# Power_Supply.net
KiCad netlist of a schematic drawn in Altium Designer
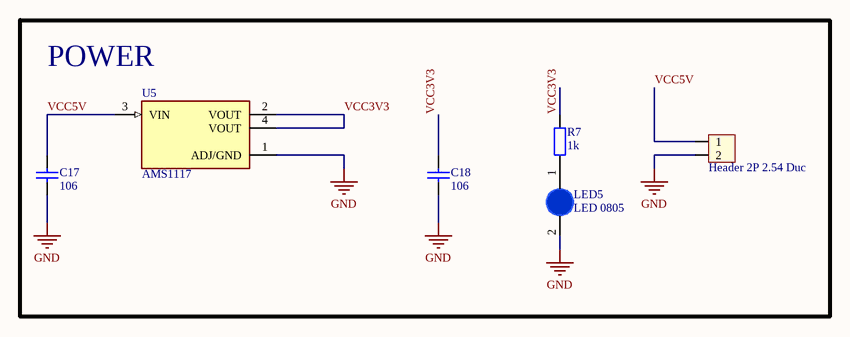
[diagram p0: Power_Supply.SchDoc]

(export (version "E")
  (design (tool "Eeschema 10.0.6"))
  (components
    (comp (ref "C17")
      (value "106")
      (footprint "tu 0603")
      (description "Dán")
      (libsource (lib "Tu dien") (part "Tu 0603 106 16V 20%"))
    )
    (comp (ref "C18")
      (value "106")
      (footprint "tu 0603")
      (description "Dán")
      (libsource (lib "Tu dien") (part "Tu 0603 106 16V 20%"))
    )
    (comp (ref "H2")
      (value "Header 2P 2.54 Duc")
      (footprint "XH2.54M-2")
      (description "Cắm")
      (libsource (lib "Header") (part "Header 2P 2.54 Duc Thang"))
    )
    (comp (ref "LED5")
      (value "LED 0805")
      (footprint "LED-0805-Blue")
      (description "Dán")
      (libsource (lib "Led") (part "LED 0805 Xanh Duong"))
    )
    (comp (ref "R7")
      (value "1k")
      (footprint "tro smd 0603")
      (description "Dán")
      (libsource (lib "Dien Tro") (part "Tro 0603 1% 1k"))
    )
    (comp (ref "U5")
      (value "AMS1117")
      (footprint "SOT229P700X180-4N")
      (description "1A LOW DROPOUT VOLTAGE REGULATOR SOT-223")
      (fields (field (name "MF") "Advanced Monolithic Systems"))
      (libsource (lib "AMS1117") (part "AMS1117"))
    )
  )
  (nets
    (net (code "1") (name "/VCC3V3") (class "Default")
      (node (ref "C18") (pin "1") (pinfunction "1_1") (pintype "passive"))
      (node (ref "R7") (pin "2") (pinfunction "2_2") (pintype "passive"))
      (node (ref "U5") (pin "2") (pinfunction "VOUT_2") (pintype "passive"))
      (node (ref "U5") (pin "4") (pinfunction "VOUT_4") (pintype "passive"))
    )
    (net (code "2") (name "/VCC5V") (class "Default")
      (node (ref "C17") (pin "1") (pinfunction "1_1") (pintype "passive"))
      (node (ref "H2") (pin "1") (pinfunction "1_1") (pintype "passive"))
      (node (ref "U5") (pin "3") (pinfunction "VIN_3") (pintype "input"))
    )
    (net (code "3") (name "GND") (class "Default")
      (node (ref "C17") (pin "2") (pinfunction "2_2") (pintype "passive"))
      (node (ref "C18") (pin "2") (pinfunction "2_2") (pintype "passive"))
      (node (ref "H2") (pin "2") (pinfunction "2_2") (pintype "passive"))
      (node (ref "LED5") (pin "2") (pinfunction "K_2") (pintype "passive"))
      (node (ref "U5") (pin "1") (pinfunction "ADJ/GND_1") (pintype "power_in"))
    )
    (net (code "4") (name "Net-(LED5-A)") (class "Default")
      (node (ref "LED5") (pin "1") (pinfunction "A_1") (pintype "passive"))
      (node (ref "R7") (pin "1") (pinfunction "1_1") (pintype "passive"))
    )
  )
)
